# TUDSSL_condenar__Hardware_PCBs_PowerModu.net
KiCad netlist of a schematic drawn in Altium Designer
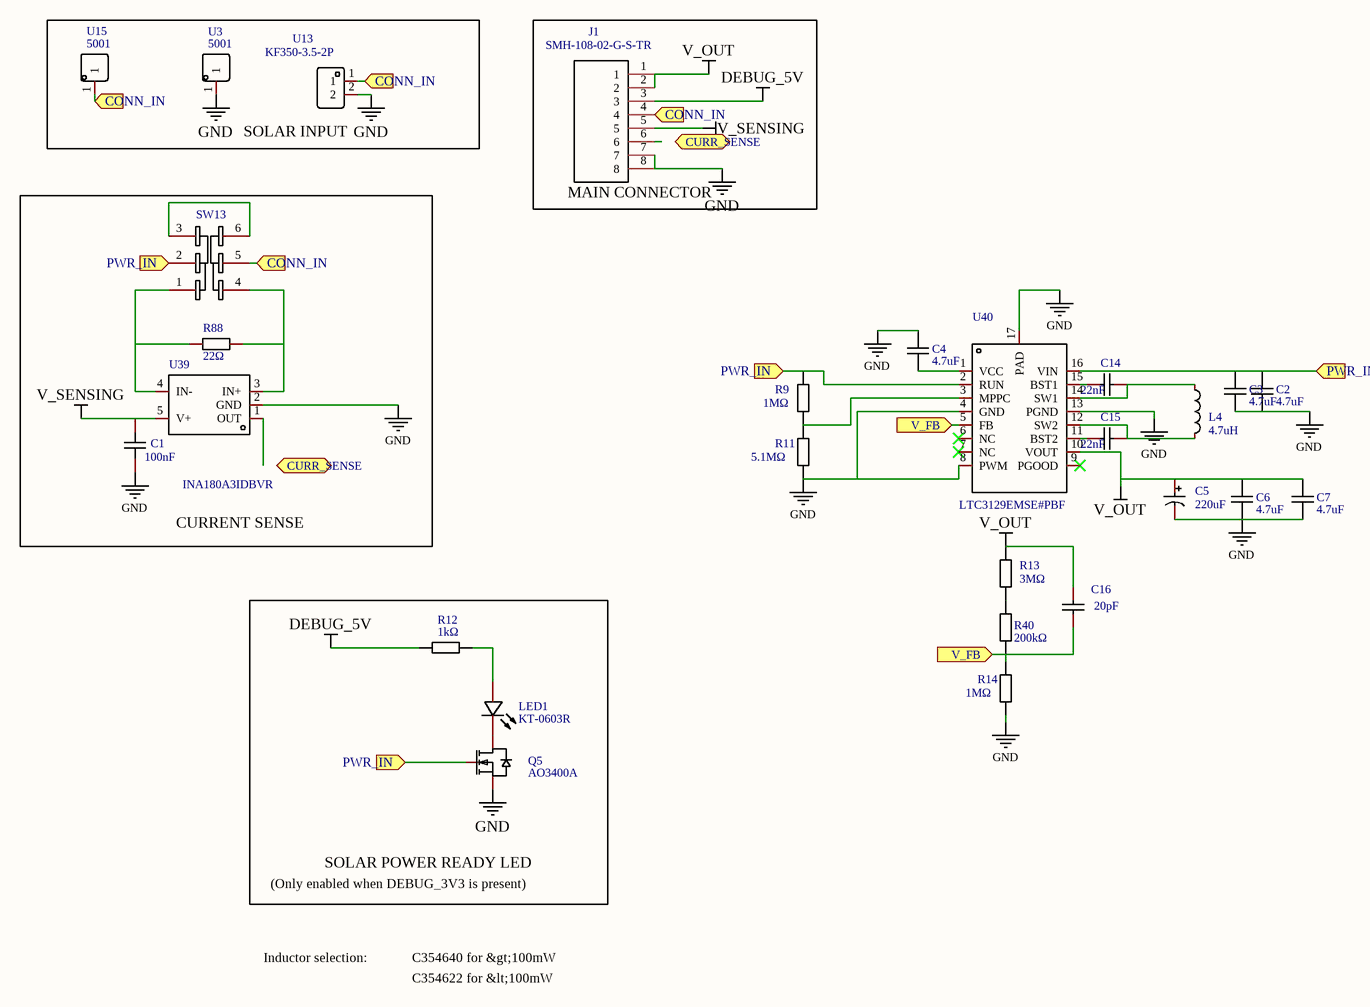
[diagram p0: TUDSSL_condenar__Hardware_PCBs_PowerModules_SolarModule_TUD-EHC-SolarModule_1__1_Main.schdoc]

(export (version "E")
  (design (tool "Eeschema 10.0.6"))
  (components
    (comp (ref "C1")
      (value "100nF")
      (fields
        (field (name "NAME") "100nF")
        (field (name "MANUFACTURER") "YAGEO")
        (field (name "MANUFACTURER PART") "CC0603KRX7R9BB104")
      )
      (libsource (lib "altium-import") (part "root_1_CC0603KRX7R9BB104_"))
    )
    (comp (ref "C2")
      (value "4.7uF")
      (fields
        (field (name "NAME") "4.7uF")
        (field (name "MANUFACTURER PART") "CL10A475KO8NNNC")
        (field (name "MANUFACTURER") "SAMSUNG")
      )
      (libsource (lib "altium-import") (part "root_1_CL10A475KO8NNNC_"))
    )
    (comp (ref "C3")
      (value "4.7uF")
      (fields
        (field (name "NAME") "4.7uF")
        (field (name "MANUFACTURER PART") "CL10A475KO8NNNC")
        (field (name "MANUFACTURER") "SAMSUNG")
      )
      (libsource (lib "altium-import") (part "root_1_CL10A475KO8NNNC_"))
    )
    (comp (ref "C4")
      (value "4.7uF")
      (fields
        (field (name "NAME") "4.7uF")
        (field (name "MANUFACTURER PART") "CL10A475KO8NNNC")
        (field (name "MANUFACTURER") "SAMSUNG")
      )
      (libsource (lib "altium-import") (part "root_1_CL10A475KO8NNNC_"))
    )
    (comp (ref "C5")
      (value "220uF")
      (fields
        (field (name "NAME") "220uF")
        (field (name "MANUFACTURER") "HONOR")
        (field (name "MANUFACTURER PART") "RVT1A221M0605")
      )
      (libsource (lib "altium-import") (part "root_0_RVT1A221M0605_"))
    )
    (comp (ref "C6")
      (value "4.7uF")
      (fields
        (field (name "NAME") "4.7uF")
        (field (name "MANUFACTURER PART") "CL10A475KO8NNNC")
        (field (name "MANUFACTURER") "SAMSUNG")
      )
      (libsource (lib "altium-import") (part "root_1_CL10A475KO8NNNC_"))
    )
    (comp (ref "C7")
      (value "4.7uF")
      (fields
        (field (name "NAME") "4.7uF")
        (field (name "MANUFACTURER PART") "CL10A475KO8NNNC")
        (field (name "MANUFACTURER") "SAMSUNG")
      )
      (libsource (lib "altium-import") (part "root_1_CL10A475KO8NNNC_"))
    )
    (comp (ref "C14")
      (value "22nF")
      (fields
        (field (name "MANUFACTURER") "SAMSUNG(三星)")
        (field (name "MANUFACTURER PART") "CL10B223KB8NNNC")
        (field (name "TOLERANCE") "±10%")
      )
      (libsource (lib "altium-import") (part "root_0_CL10B223KB8NNNC_"))
    )
    (comp (ref "C15")
      (value "22nF")
      (fields
        (field (name "MANUFACTURER") "SAMSUNG(三星)")
        (field (name "MANUFACTURER PART") "CL10B223KB8NNNC")
        (field (name "TOLERANCE") "±10%")
      )
      (libsource (lib "altium-import") (part "root_0_CL10B223KB8NNNC_"))
    )
    (comp (ref "C16")
      (value "20pF")
      (fields
        (field (name "MANUFACTURER") "SAMSUNG(三星)")
        (field (name "MANUFACTURER PART") "CL10C200JB8NNNC")
        (field (name "TOLERANCE") "±5%")
      )
      (libsource (lib "altium-import") (part "root_1_CL10C200JB8NNNC_"))
    )
    (comp (ref "J1")
      (value "SMH-108-02-G-S-TR")
      (fields (field (name "NAME") "SMH-108-02-G-S-TR"))
      (libsource (lib "altium-import") (part "root_0_SMH-108-02-G-S-TR_"))
    )
    (comp (ref "L4")
      (value "4.7uH")
      (fields (field (name "MANUFACTURER") "Sunlord(顺络)") (field (name "MANUFACTURER PART") "SWPA5040S4R7NT"))
      (libsource (lib "altium-import") (part "root_3_SWPA5040S4R7NT_"))
    )
    (comp (ref "LED1")
      (value "KT-0603R")
      (fields (field (name "NAME") "KT-0603R") (field (name "MANUFACTURER") "KENTO"))
      (libsource (lib "altium-import") (part "root_1_KT-0603R_"))
    )
    (comp (ref "Q5")
      (value "AO3400A")
      (fields (field (name "NAME") "AO3400A") (field (name "MANUFACTURER") "AOS"))
      (libsource (lib "altium-import") (part "root_0_AO3400A_"))
    )
    (comp (ref "R9")
      (value "1MΩ")
      (fields
        (field (name "NAME") "1MΩ")
        (field (name "MANUFACTURER") "UniOhm")
        (field (name "MANUFACTURER PART") "0603WAF1004T5E")
      )
      (libsource (lib "altium-import") (part "root_1_0603WAF1004T5E_"))
    )
    (comp (ref "R11")
      (value "5.1MΩ")
      (fields
        (field (name "NAME") "5.1MΩ")
        (field (name "MANUFACTURER") "UniOhm")
        (field (name "MANUFACTURER PART") "0603WAF5104T5E")
      )
      (libsource (lib "altium-import") (part "root_1_0603WAF5104T5E_"))
    )
    (comp (ref "R12")
      (value "1kΩ")
      (fields
        (field (name "NAME") "1kΩ")
        (field (name "MANUFACTURER") "UniOhm")
        (field (name "MANUFACTURER PART") "0603WAF1001T5E")
      )
      (libsource (lib "altium-import") (part "root_0_0603WAF1001T5E_"))
    )
    (comp (ref "R13")
      (value "3MΩ")
      (fields
        (field (name "NAME") "3MΩ")
        (field (name "MANUFACTURER") "UniOhm")
        (field (name "MANUFACTURER PART") "0603WAF3004T5E")
      )
      (libsource (lib "altium-import") (part "root_1_0603WAF3004T5E_"))
    )
    (comp (ref "R14")
      (value "1MΩ")
      (fields
        (field (name "NAME") "1MΩ")
        (field (name "MANUFACTURER") "UniOhm")
        (field (name "MANUFACTURER PART") "0603WAF1004T5E")
      )
      (libsource (lib "altium-import") (part "root_1_0603WAF1004T5E_"))
    )
    (comp (ref "R40")
      (value "200kΩ")
      (fields
        (field (name "NAME") "200kΩ")
        (field (name "MANUFACTURER") "UniOhm")
        (field (name "MANUFACTURER PART") "0603WAF2003T5E")
      )
      (libsource (lib "altium-import") (part "root_3_0603WAF2003T5E_"))
    )
    (comp (ref "R88")
      (value "22Ω")
      (fields
        (field (name "MANUFACTURER") "UNI-ROYAL(厚声)")
        (field (name "MANUFACTURER PART") "0603WAF220JT5E")
        (field (name "TOLERANCE") "±1%")
      )
      (libsource (lib "altium-import") (part "root_0_0603WAF220JT5E_"))
    )
    (comp (ref "SW13")
      (value "K3-2235D-F1")
      (fields (field (name "MANUFACTURER") "韩国韩荣"))
      (libsource (lib "altium-import") (part "root_1_K3-2235D-F1_"))
    )
    (comp (ref "U3")
      (value "5001")
      (fields (field (name "NAME") "5001") (field (name "MANUFACTURER") "Keystone"))
      (libsource (lib "altium-import") (part "root_1_5001_"))
    )
    (comp (ref "U13")
      (value "KF350-3.5-2P")
      (fields (field (name "NAME") "KF350-3.5-2P") (field (name "MANUFACTURER") "Cixi Kefa Elec"))
      (libsource (lib "altium-import") (part "root_2_KF350-3.5-2P_"))
    )
    (comp (ref "U15")
      (value "5001")
      (fields (field (name "NAME") "5001") (field (name "MANUFACTURER") "Keystone"))
      (libsource (lib "altium-import") (part "root_1_5001_"))
    )
    (comp (ref "U39")
      (value "INA180A3IDBVR")
      (fields (field (name "LCSC PART NAME") "INA180A3IDBVR") (field (name "MANUFACTURER") "TI(德州仪器)"))
      (libsource (lib "altium-import") (part "root_2_INA180A3IDBVR_"))
    )
    (comp (ref "U40")
      (value "LTC3129EMSE-1#PBF")
      (fields
        (field (name "LCSC PART NAME") "LTC3129EMSE#PBF")
        (field (name "MANUFACTURER") "ADI(亚德诺)/LINEAR")
        (field (name "MANUFACTURER PART") "LTC3129EMSE#PBF")
      )
      (libsource (lib "altium-import") (part "root_0_LTC3129EMSE-1#PBF_"))
    )
  )
  (nets
    (net (code "1") (name "/CONN_IN") (class "Default")
      (node (ref "J1") (pin "4") (pinfunction "4_4") (pintype "passive"))
      (node (ref "SW13") (pin "5") (pinfunction "5_5") (pintype "passive"))
      (node (ref "U13") (pin "1") (pinfunction "1_1") (pintype "passive"))
      (node (ref "U15") (pin "1") (pinfunction "1_1") (pintype "passive"))
    )
    (net (code "3") (name "/PWR_IN") (class "Default")
      (node (ref "C2") (pin "2") (pinfunction "2_2") (pintype "passive"))
      (node (ref "C3") (pin "2") (pinfunction "2_2") (pintype "passive"))
      (node (ref "Q5") (pin "1") (pinfunction "G_1") (pintype "passive"))
      (node (ref "R9") (pin "2") (pinfunction "2_2") (pintype "passive"))
      (node (ref "SW13") (pin "2") (pinfunction "2_2") (pintype "passive"))
      (node (ref "U40") (pin "16") (pinfunction "VIN_16") (pintype "passive"))
      (node (ref "U40") (pin "2") (pinfunction "RUN_2") (pintype "passive"))
    )
    (net (code "4") (name "/V_FB") (class "Default")
      (node (ref "C16") (pin "1") (pinfunction "1_1") (pintype "passive"))
      (node (ref "R14") (pin "2") (pinfunction "2_2") (pintype "passive"))
      (node (ref "R40") (pin "2") (pinfunction "2_2") (pintype "passive"))
      (node (ref "U40") (pin "5") (pinfunction "FB_5") (pintype "passive"))
    )
    (net (code "5") (name "DEBUG_5V") (class "Default")
      (node (ref "J1") (pin "3") (pinfunction "3_3") (pintype "passive"))
      (node (ref "R12") (pin "1") (pinfunction "1_1") (pintype "passive"))
    )
    (net (code "6") (name "GND") (class "Default")
      (node (ref "C1") (pin "1") (pinfunction "1_1") (pintype "passive"))
      (node (ref "C2") (pin "1") (pinfunction "1_1") (pintype "passive"))
      (node (ref "C3") (pin "1") (pinfunction "1_1") (pintype "passive"))
      (node (ref "C4") (pin "2") (pinfunction "2_2") (pintype "passive"))
      (node (ref "C5") (pin "2") (pinfunction "2_2") (pintype "passive"))
      (node (ref "C6") (pin "1") (pinfunction "1_1") (pintype "passive"))
      (node (ref "C7") (pin "1") (pinfunction "1_1") (pintype "passive"))
      (node (ref "J1") (pin "7") (pinfunction "7_7") (pintype "passive"))
      (node (ref "J1") (pin "8") (pinfunction "8_8") (pintype "passive"))
      (node (ref "Q5") (pin "2") (pinfunction "S_2") (pintype "passive"))
      (node (ref "R11") (pin "2") (pinfunction "2_2") (pintype "passive"))
      (node (ref "R14") (pin "1") (pinfunction "1_1") (pintype "passive"))
      (node (ref "U13") (pin "2") (pinfunction "2_2") (pintype "passive"))
      (node (ref "U3") (pin "1") (pinfunction "1_1") (pintype "passive"))
      (node (ref "U39") (pin "2") (pinfunction "GND_2") (pintype "passive"))
      (node (ref "U40") (pin "13") (pinfunction "PGND_13") (pintype "passive"))
      (node (ref "U40") (pin "17") (pinfunction "PAD_17") (pintype "passive"))
      (node (ref "U40") (pin "4") (pinfunction "GND_4") (pintype "passive"))
      (node (ref "U40") (pin "8") (pinfunction "PWM_8") (pintype "passive"))
    )
    (net (code "7") (name "Net-(LED1-A)") (class "Default")
      (node (ref "LED1") (pin "1") (pinfunction "A_1") (pintype "passive"))
      (node (ref "R12") (pin "2") (pinfunction "2_2") (pintype "passive"))
    )
    (net (code "8") (name "Net-(LED1-K)") (class "Default")
      (node (ref "LED1") (pin "2") (pinfunction "K_2") (pintype "passive"))
      (node (ref "Q5") (pin "3") (pinfunction "D_3") (pintype "passive"))
    )
    (net (code "9") (name "Net-(R13-Pad1)") (class "Default")
      (node (ref "R13") (pin "1") (pinfunction "1_1") (pintype "passive"))
      (node (ref "R40") (pin "1") (pinfunction "1_1") (pintype "passive"))
    )
    (net (code "10") (name "Net-(SW13-Pad3)") (class "Default")
      (node (ref "SW13") (pin "3") (pinfunction "3_3") (pintype "passive"))
      (node (ref "SW13") (pin "6") (pinfunction "6_6") (pintype "passive"))
    )
    (net (code "11") (name "Net-(U39-IN+)") (class "Default")
      (node (ref "R88") (pin "2") (pinfunction "2_2") (pintype "passive"))
      (node (ref "SW13") (pin "4") (pinfunction "4_4") (pintype "passive"))
      (node (ref "U39") (pin "3") (pinfunction "IN+_3") (pintype "passive"))
    )
    (net (code "12") (name "Net-(U39-IN-)") (class "Default")
      (node (ref "R88") (pin "1") (pinfunction "1_1") (pintype "passive"))
      (node (ref "SW13") (pin "1") (pinfunction "1_1") (pintype "passive"))
      (node (ref "U39") (pin "4") (pinfunction "IN-_4") (pintype "passive"))
    )
    (net (code "13") (name "Net-(U40-BST1)") (class "Default")
      (node (ref "C14") (pin "1") (pinfunction "1_1") (pintype "passive"))
      (node (ref "U40") (pin "15") (pinfunction "BST1_15") (pintype "passive"))
    )
    (net (code "14") (name "Net-(U40-BST2)") (class "Default")
      (node (ref "C15") (pin "1") (pinfunction "1_1") (pintype "passive"))
      (node (ref "U40") (pin "11") (pinfunction "BST2_11") (pintype "passive"))
    )
    (net (code "15") (name "Net-(U40-MPPC)") (class "Default")
      (node (ref "R11") (pin "1") (pinfunction "1_1") (pintype "passive"))
      (node (ref "R9") (pin "1") (pinfunction "1_1") (pintype "passive"))
      (node (ref "U40") (pin "3") (pinfunction "MPPC_3") (pintype "passive"))
    )
    (net (code "16") (name "Net-(U40-SW1)") (class "Default")
      (node (ref "C14") (pin "2") (pinfunction "2_2") (pintype "passive"))
      (node (ref "L4") (pin "1") (pinfunction "1_1") (pintype "passive"))
      (node (ref "U40") (pin "14") (pinfunction "SW1_14") (pintype "passive"))
    )
    (net (code "17") (name "Net-(U40-SW2)") (class "Default")
      (node (ref "C15") (pin "2") (pinfunction "2_2") (pintype "passive"))
      (node (ref "L4") (pin "2") (pinfunction "2_2") (pintype "passive"))
      (node (ref "U40") (pin "12") (pinfunction "SW2_12") (pintype "passive"))
    )
    (net (code "18") (name "Net-(U40-VCC)") (class "Default")
      (node (ref "C4") (pin "1") (pinfunction "1_1") (pintype "passive"))
      (node (ref "U40") (pin "1") (pinfunction "VCC_1") (pintype "passive"))
    )
    (net (code "19") (name "V_OUT") (class "Default")
      (node (ref "C16") (pin "2") (pinfunction "2_2") (pintype "passive"))
      (node (ref "C5") (pin "1") (pinfunction "1_1") (pintype "passive"))
      (node (ref "C6") (pin "2") (pinfunction "2_2") (pintype "passive"))
      (node (ref "C7") (pin "2") (pinfunction "2_2") (pintype "passive"))
      (node (ref "J1") (pin "1") (pinfunction "1_1") (pintype "passive"))
      (node (ref "J1") (pin "2") (pinfunction "2_2") (pintype "passive"))
      (node (ref "R13") (pin "2") (pinfunction "2_2") (pintype "passive"))
      (node (ref "U40") (pin "10") (pinfunction "VOUT_10") (pintype "passive"))
    )
    (net (code "20") (name "V_SENSING") (class "Default")
      (node (ref "C1") (pin "2") (pinfunction "2_2") (pintype "passive"))
      (node (ref "J1") (pin "5") (pinfunction "5_5") (pintype "passive"))
      (node (ref "U39") (pin "5") (pinfunction "V+_5") (pintype "passive"))
    )
    (net (code "21") (name "unconnected-(J1-Pad6)") (class "Default")
      (node (ref "J1") (pin "6") (pinfunction "6_6") (pintype "passive"))
    )
    (net (code "22") (name "unconnected-(U39-OUT-Pad1)") (class "Default")
      (node (ref "U39") (pin "1") (pinfunction "OUT_1") (pintype "passive"))
    )
    (net (code "23") (name "unconnected-(U40-NC-Pad6)") (class "Default")
      (node (ref "U40") (pin "6") (pinfunction "NC_6") (pintype "passive+no_connect"))
    )
    (net (code "24") (name "unconnected-(U40-NC-Pad7)") (class "Default")
      (node (ref "U40") (pin "7") (pinfunction "NC_7") (pintype "passive+no_connect"))
    )
    (net (code "25") (name "unconnected-(U40-PGOOD-Pad9)") (class "Default")
      (node (ref "U40") (pin "9") (pinfunction "PGOOD_9") (pintype "passive+no_connect"))
    )
  )
)
